# ArduFrauenfelderCNC_0_1-b9.net
KiCad netlist of a schematic drawn in EAGLE
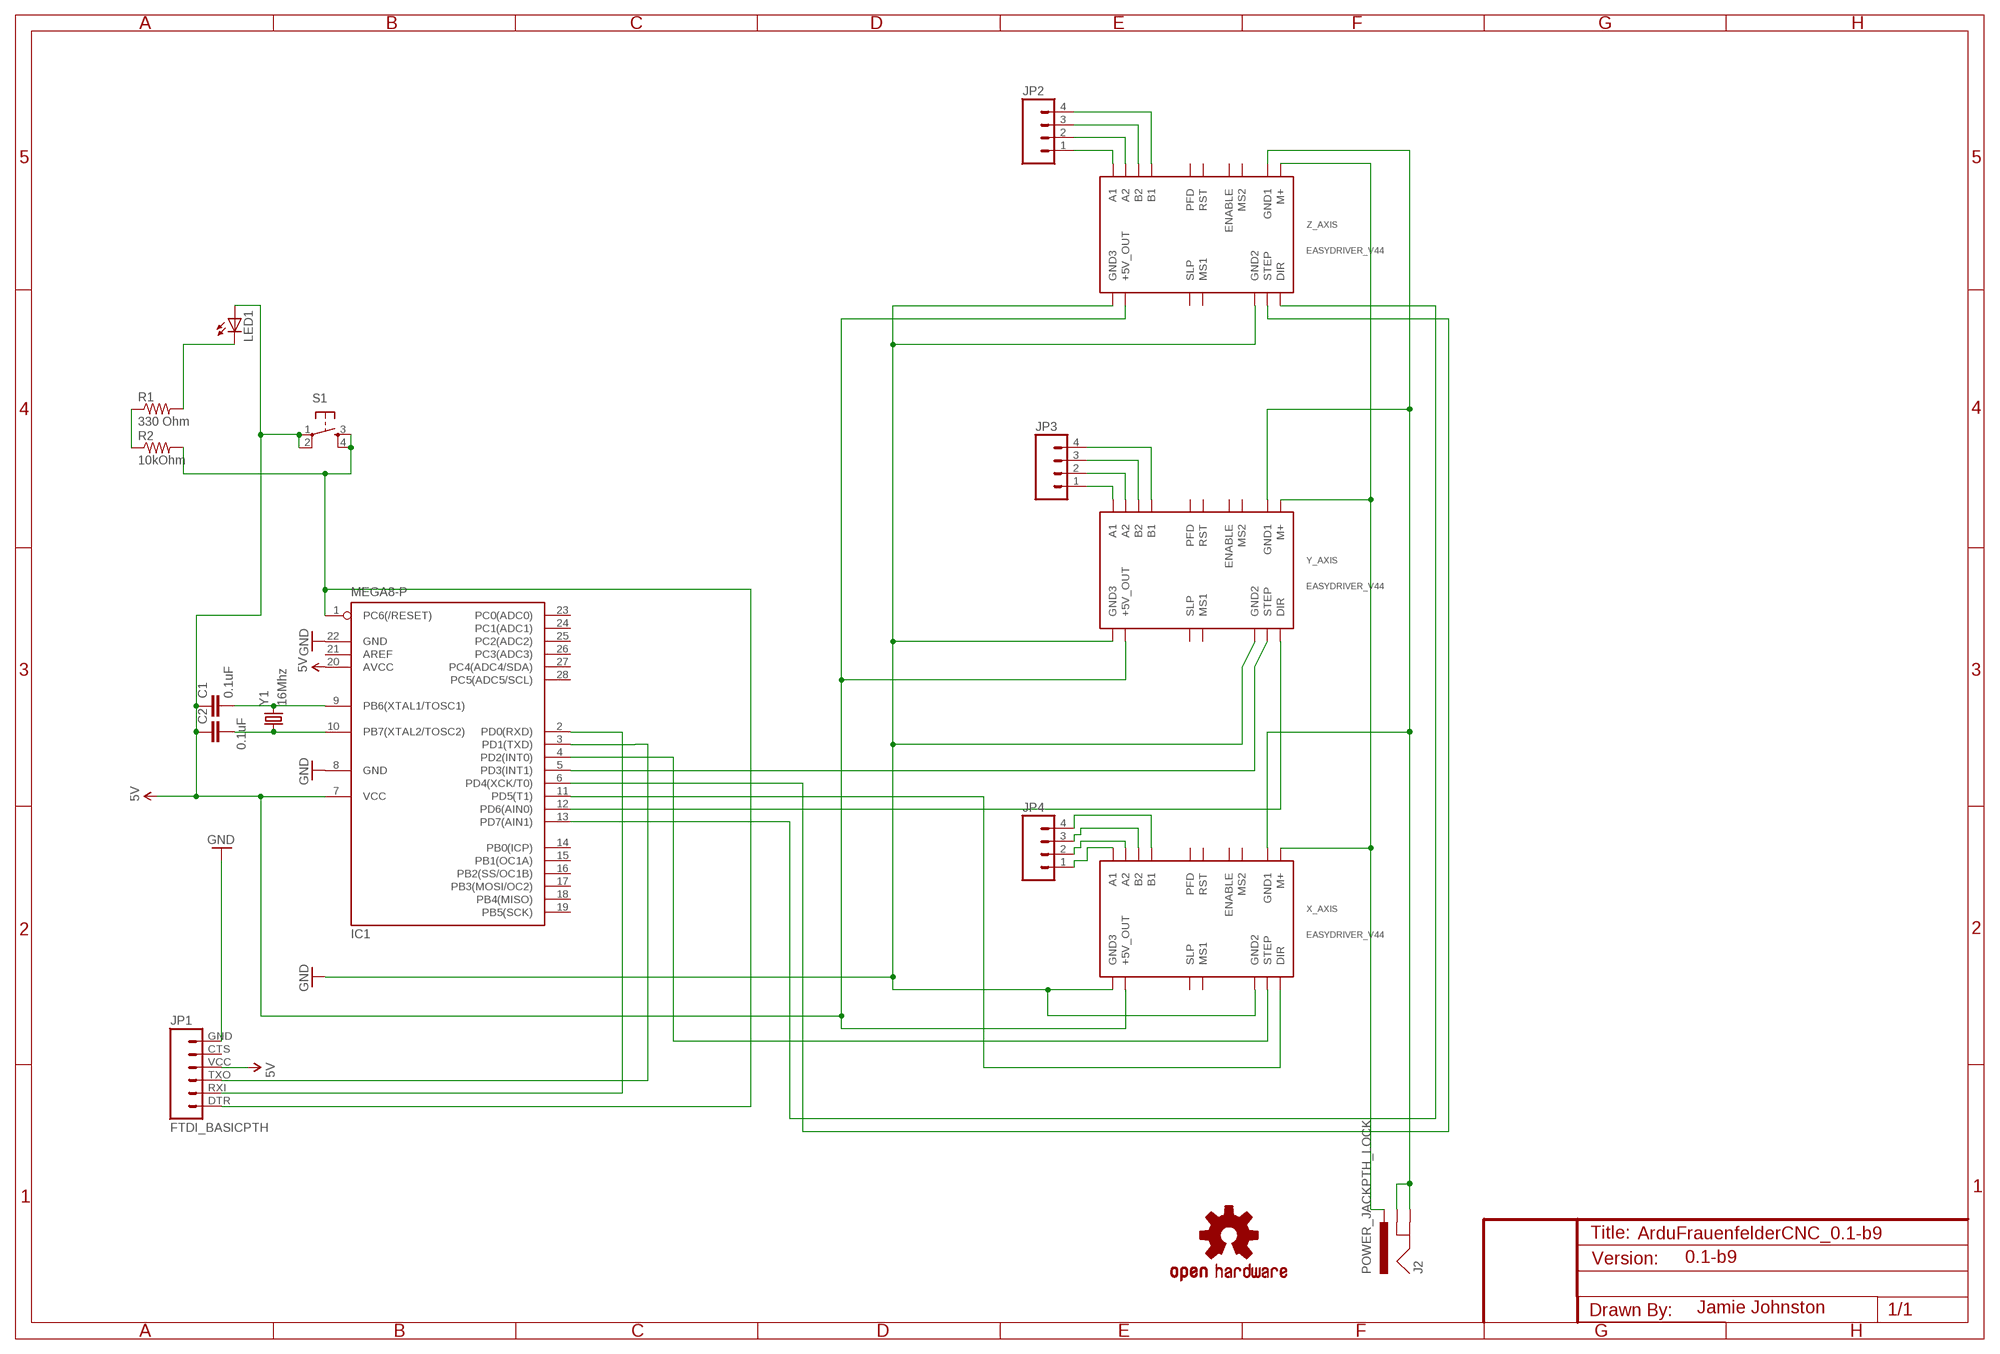
[diagram p0: schematic, sheet 1]

(export (version "E")
  (design (tool "Eeschema 10.0.6"))
  (components
    (comp (ref "C1")
      (value "0.1uF")
      (footprint "eagle-import:CAP-PTH-SMALL")
      (libsource (lib "eagle-import") (part "CAPPTH"))
    )
    (comp (ref "C2")
      (value "0.1uF")
      (footprint "eagle-import:CAP-PTH-SMALL")
      (libsource (lib "eagle-import") (part "CAPPTH"))
    )
    (comp (ref "IC1")
      (value "MEGA8-P")
      (footprint "eagle-import:DIL28-3")
      (libsource (lib "eagle-import") (part "MEGA8-P"))
    )
    (comp (ref "J2")
      (value "POWER_JACKPTH_LOCK")
      (footprint "eagle-import:POWER_JACK_PTH_LOCK")
      (libsource (lib "eagle-import") (part "POWER_JACKPTH_LOCK"))
    )
    (comp (ref "JP1")
      (value "FTDI_BASICPTH")
      (footprint "eagle-import:FTDI_BASIC")
      (libsource (lib "eagle-import") (part "FTDI_BASICPTH"))
    )
    (comp (ref "JP2")
      (value "M04LOCK")
      (footprint "eagle-import:1X04_LOCK")
      (libsource (lib "eagle-import") (part "M04LOCK"))
    )
    (comp (ref "JP3")
      (value "M04LOCK")
      (footprint "eagle-import:1X04_LOCK")
      (libsource (lib "eagle-import") (part "M04LOCK"))
    )
    (comp (ref "JP4")
      (value "M04LOCK")
      (footprint "eagle-import:1X04_LOCK")
      (libsource (lib "eagle-import") (part "M04LOCK"))
    )
    (comp (ref "LED1")
      (value "LED5MM")
      (footprint "eagle-import:LED5MM")
      (libsource (lib "eagle-import") (part "LED5MM"))
    )
    (comp (ref "R1")
      (value "330 Ohm")
      (footprint "eagle-import:AXIAL-0.4")
      (libsource (lib "eagle-import") (part "RESISTORPTH-1/4W"))
    )
    (comp (ref "R2")
      (value "10kOhm")
      (footprint "eagle-import:AXIAL-0.4")
      (libsource (lib "eagle-import") (part "RESISTORPTH-1/4W"))
    )
    (comp (ref "S1")
      (value "TAC_SWITCHPTH")
      (footprint "eagle-import:TACTILE-PTH")
      (libsource (lib "eagle-import") (part "TAC_SWITCHPTH"))
    )
    (comp (ref "U$2")
      (value "OSHW-LOGOL")
      (footprint "eagle-import:OSHW-LOGO-L")
      (libsource (lib "eagle-import") (part "OSHW-LOGOL"))
    )
    (comp (ref "X_AXIS")
      (value "EASYDRIVER_V44")
      (footprint "eagle-import:EASYDRIVER_V44")
      (libsource (lib "eagle-import") (part "EASYDRIVER_V44"))
    )
    (comp (ref "Y1")
      (value "16Mhz")
      (footprint "eagle-import:HC49US")
      (libsource (lib "eagle-import") (part "CRYSTALHC49US"))
    )
    (comp (ref "Y_AXIS")
      (value "EASYDRIVER_V44")
      (footprint "eagle-import:EASYDRIVER_V44")
      (libsource (lib "eagle-import") (part "EASYDRIVER_V44"))
    )
    (comp (ref "Z_AXIS")
      (value "EASYDRIVER_V44")
      (footprint "eagle-import:EASYDRIVER_V44")
      (libsource (lib "eagle-import") (part "EASYDRIVER_V44"))
    )
  )
  (nets
    (net (code "1") (name "5V") (class "Default")
      (node (ref "C1") (pin "1") (pinfunction "1_1") (pintype "passive"))
      (node (ref "C2") (pin "1") (pinfunction "1_1") (pintype "passive"))
      (node (ref "IC1") (pin "20") (pinfunction "AVCC_20") (pintype "power_in"))
      (node (ref "IC1") (pin "7") (pinfunction "VCC_7") (pintype "power_in"))
      (node (ref "JP1") (pin "VCC") (pinfunction "4_VCC") (pintype "passive"))
      (node (ref "LED1") (pin "A") (pinfunction "A_A") (pintype "passive"))
      (node (ref "S1") (pin "1") (pinfunction "1_1") (pintype "passive"))
      (node (ref "S1") (pin "2") (pinfunction "2_2") (pintype "passive"))
      (node (ref "X_AXIS") (pin "P$11") (pinfunction "+5V_OUT_P$11") (pintype "bidirectional"))
      (node (ref "Y_AXIS") (pin "P$11") (pinfunction "+5V_OUT_P$11") (pintype "bidirectional"))
      (node (ref "Z_AXIS") (pin "P$11") (pinfunction "+5V_OUT_P$11") (pintype "bidirectional"))
    )
    (net (code "2") (name "GND") (class "Default")
      (node (ref "IC1") (pin "22") (pinfunction "GND_22") (pintype "power_in"))
      (node (ref "IC1") (pin "8") (pinfunction "GND_8") (pintype "power_in"))
      (node (ref "JP1") (pin "GND") (pinfunction "6_GND") (pintype "passive"))
      (node (ref "X_AXIS") (pin "GND2") (pinfunction "GND2_GND2") (pintype "bidirectional"))
      (node (ref "X_AXIS") (pin "GND3") (pinfunction "GND3_GND3") (pintype "bidirectional"))
      (node (ref "Y_AXIS") (pin "GND2") (pinfunction "GND2_GND2") (pintype "bidirectional"))
      (node (ref "Y_AXIS") (pin "GND3") (pinfunction "GND3_GND3") (pintype "bidirectional"))
      (node (ref "Z_AXIS") (pin "GND2") (pinfunction "GND2_GND2") (pintype "bidirectional"))
      (node (ref "Z_AXIS") (pin "GND3") (pinfunction "GND3_GND3") (pintype "bidirectional"))
    )
    (net (code "3") (name "Net-(IC1-PB6(XTAL1{slash}TOSC1))") (class "Default")
      (node (ref "C1") (pin "2") (pinfunction "2_2") (pintype "passive"))
      (node (ref "IC1") (pin "9") (pinfunction "PB6(XTAL1/TOSC1)_9") (pintype "bidirectional"))
      (node (ref "Y1") (pin "2") (pinfunction "2_2") (pintype "passive"))
    )
    (net (code "4") (name "Net-(IC1-PB7(XTAL2{slash}TOSC2))") (class "Default")
      (node (ref "C2") (pin "2") (pinfunction "2_2") (pintype "passive"))
      (node (ref "IC1") (pin "10") (pinfunction "PB7(XTAL2/TOSC2)_10") (pintype "bidirectional"))
      (node (ref "Y1") (pin "1") (pinfunction "1_1") (pintype "passive"))
    )
    (net (code "5") (name "Net-(IC1-PC6({slash}RESET))") (class "Default")
      (node (ref "IC1") (pin "1") (pinfunction "PC6(/RESET)_1") (pintype "bidirectional"))
      (node (ref "JP1") (pin "DTR") (pinfunction "1_DTR") (pintype "passive"))
      (node (ref "R2") (pin "P$2") (pinfunction "2_P$2") (pintype "passive"))
      (node (ref "S1") (pin "3") (pinfunction "3_3") (pintype "passive"))
      (node (ref "S1") (pin "4") (pinfunction "4_4") (pintype "passive"))
    )
    (net (code "6") (name "Net-(IC1-PD0(RXD))") (class "Default")
      (node (ref "IC1") (pin "2") (pinfunction "PD0(RXD)_2") (pintype "bidirectional"))
      (node (ref "JP1") (pin "RXI") (pinfunction "2_RXI") (pintype "passive"))
    )
    (net (code "7") (name "Net-(IC1-PD1(TXD))") (class "Default")
      (node (ref "IC1") (pin "3") (pinfunction "PD1(TXD)_3") (pintype "bidirectional"))
      (node (ref "JP1") (pin "TXO") (pinfunction "3_TXO") (pintype "passive"))
    )
    (net (code "8") (name "Net-(IC1-PD2(INT0))") (class "Default")
      (node (ref "IC1") (pin "4") (pinfunction "PD2(INT0)_4") (pintype "bidirectional"))
      (node (ref "X_AXIS") (pin "STEP") (pinfunction "STEP_STEP") (pintype "bidirectional"))
    )
    (net (code "9") (name "Net-(IC1-PD3(INT1))") (class "Default")
      (node (ref "IC1") (pin "5") (pinfunction "PD3(INT1)_5") (pintype "bidirectional"))
      (node (ref "Y_AXIS") (pin "STEP") (pinfunction "STEP_STEP") (pintype "bidirectional"))
    )
    (net (code "10") (name "Net-(IC1-PD4(XCK{slash}T0))") (class "Default")
      (node (ref "IC1") (pin "6") (pinfunction "PD4(XCK/T0)_6") (pintype "bidirectional"))
      (node (ref "Z_AXIS") (pin "STEP") (pinfunction "STEP_STEP") (pintype "bidirectional"))
    )
    (net (code "11") (name "Net-(IC1-PD5(T1))") (class "Default")
      (node (ref "IC1") (pin "11") (pinfunction "PD5(T1)_11") (pintype "bidirectional"))
      (node (ref "X_AXIS") (pin "DIR") (pinfunction "DIR_DIR") (pintype "bidirectional"))
    )
    (net (code "12") (name "Net-(IC1-PD6(AIN0))") (class "Default")
      (node (ref "IC1") (pin "12") (pinfunction "PD6(AIN0)_12") (pintype "bidirectional"))
      (node (ref "Y_AXIS") (pin "DIR") (pinfunction "DIR_DIR") (pintype "bidirectional"))
    )
    (net (code "13") (name "Net-(IC1-PD7(AIN1))") (class "Default")
      (node (ref "IC1") (pin "13") (pinfunction "PD7(AIN1)_13") (pintype "bidirectional"))
      (node (ref "Z_AXIS") (pin "DIR") (pinfunction "DIR_DIR") (pintype "bidirectional"))
    )
    (net (code "14") (name "Net-(J2-PadGND)") (class "Default")
      (node (ref "J2") (pin "GND") (pinfunction "GND_GND") (pintype "bidirectional"))
      (node (ref "J2") (pin "GNDBREAK") (pinfunction "GNDBREAK_GNDBREAK") (pintype "bidirectional"))
      (node (ref "X_AXIS") (pin "GND1") (pinfunction "GND1_GND1") (pintype "bidirectional"))
      (node (ref "Y_AXIS") (pin "GND1") (pinfunction "GND1_GND1") (pintype "bidirectional"))
      (node (ref "Z_AXIS") (pin "GND1") (pinfunction "GND1_GND1") (pintype "bidirectional"))
    )
    (net (code "15") (name "Net-(J2-PadPWR)") (class "Default")
      (node (ref "J2") (pin "PWR") (pinfunction "PWR_PWR") (pintype "bidirectional"))
      (node (ref "X_AXIS") (pin "M+") (pinfunction "M+_M+") (pintype "bidirectional"))
      (node (ref "Y_AXIS") (pin "M+") (pinfunction "M+_M+") (pintype "bidirectional"))
      (node (ref "Z_AXIS") (pin "M+") (pinfunction "M+_M+") (pintype "bidirectional"))
    )
    (net (code "16") (name "Net-(JP2-Pad1)") (class "Default")
      (node (ref "JP2") (pin "1") (pinfunction "1_1") (pintype "passive"))
      (node (ref "Z_AXIS") (pin "A1") (pinfunction "A1_A1") (pintype "bidirectional"))
    )
    (net (code "17") (name "Net-(JP2-Pad2)") (class "Default")
      (node (ref "JP2") (pin "2") (pinfunction "2_2") (pintype "passive"))
      (node (ref "Z_AXIS") (pin "A2") (pinfunction "A2_A2") (pintype "bidirectional"))
    )
    (net (code "18") (name "Net-(JP2-Pad3)") (class "Default")
      (node (ref "JP2") (pin "3") (pinfunction "3_3") (pintype "passive"))
      (node (ref "Z_AXIS") (pin "B2") (pinfunction "B2_B2") (pintype "bidirectional"))
    )
    (net (code "19") (name "Net-(JP2-Pad4)") (class "Default")
      (node (ref "JP2") (pin "4") (pinfunction "4_4") (pintype "passive"))
      (node (ref "Z_AXIS") (pin "B1") (pinfunction "B1_B1") (pintype "bidirectional"))
    )
    (net (code "20") (name "Net-(JP3-Pad1)") (class "Default")
      (node (ref "JP3") (pin "1") (pinfunction "1_1") (pintype "passive"))
      (node (ref "Y_AXIS") (pin "A1") (pinfunction "A1_A1") (pintype "bidirectional"))
    )
    (net (code "21") (name "Net-(JP3-Pad2)") (class "Default")
      (node (ref "JP3") (pin "2") (pinfunction "2_2") (pintype "passive"))
      (node (ref "Y_AXIS") (pin "A2") (pinfunction "A2_A2") (pintype "bidirectional"))
    )
    (net (code "22") (name "Net-(JP3-Pad3)") (class "Default")
      (node (ref "JP3") (pin "3") (pinfunction "3_3") (pintype "passive"))
      (node (ref "Y_AXIS") (pin "B2") (pinfunction "B2_B2") (pintype "bidirectional"))
    )
    (net (code "23") (name "Net-(JP3-Pad4)") (class "Default")
      (node (ref "JP3") (pin "4") (pinfunction "4_4") (pintype "passive"))
      (node (ref "Y_AXIS") (pin "B1") (pinfunction "B1_B1") (pintype "bidirectional"))
    )
    (net (code "24") (name "Net-(JP4-Pad1)") (class "Default")
      (node (ref "JP4") (pin "1") (pinfunction "1_1") (pintype "passive"))
      (node (ref "X_AXIS") (pin "A1") (pinfunction "A1_A1") (pintype "bidirectional"))
    )
    (net (code "25") (name "Net-(JP4-Pad2)") (class "Default")
      (node (ref "JP4") (pin "2") (pinfunction "2_2") (pintype "passive"))
      (node (ref "X_AXIS") (pin "A2") (pinfunction "A2_A2") (pintype "bidirectional"))
    )
    (net (code "26") (name "Net-(JP4-Pad3)") (class "Default")
      (node (ref "JP4") (pin "3") (pinfunction "3_3") (pintype "passive"))
      (node (ref "X_AXIS") (pin "B2") (pinfunction "B2_B2") (pintype "bidirectional"))
    )
    (net (code "27") (name "Net-(JP4-Pad4)") (class "Default")
      (node (ref "JP4") (pin "4") (pinfunction "4_4") (pintype "passive"))
      (node (ref "X_AXIS") (pin "B1") (pinfunction "B1_B1") (pintype "bidirectional"))
    )
    (net (code "28") (name "Net-(LED1-C)") (class "Default")
      (node (ref "LED1") (pin "K") (pinfunction "C_K") (pintype "passive"))
      (node (ref "R1") (pin "P$2") (pinfunction "2_P$2") (pintype "passive"))
    )
    (net (code "29") (name "Net-(R1-1)") (class "Default")
      (node (ref "R1") (pin "P$1") (pinfunction "1_P$1") (pintype "passive"))
      (node (ref "R2") (pin "P$1") (pinfunction "1_P$1") (pintype "passive"))
    )
    (net (code "30") (name "unconnected-(IC1-AREF-Pad21)") (class "Default")
      (node (ref "IC1") (pin "21") (pinfunction "AREF_21") (pintype "passive"))
    )
    (net (code "31") (name "unconnected-(IC1-PB0(ICP)-Pad14)") (class "Default")
      (node (ref "IC1") (pin "14") (pinfunction "PB0(ICP)_14") (pintype "bidirectional"))
    )
    (net (code "32") (name "unconnected-(IC1-PB1(OC1A)-Pad15)") (class "Default")
      (node (ref "IC1") (pin "15") (pinfunction "PB1(OC1A)_15") (pintype "bidirectional"))
    )
    (net (code "33") (name "unconnected-(IC1-PB2(SS{slash}OC1B)-Pad16)") (class "Default")
      (node (ref "IC1") (pin "16") (pinfunction "PB2(SS/OC1B)_16") (pintype "bidirectional"))
    )
    (net (code "34") (name "unconnected-(IC1-PB3(MOSI{slash}OC2)-Pad17)") (class "Default")
      (node (ref "IC1") (pin "17") (pinfunction "PB3(MOSI/OC2)_17") (pintype "bidirectional"))
    )
    (net (code "35") (name "unconnected-(IC1-PB4(MISO)-Pad18)") (class "Default")
      (node (ref "IC1") (pin "18") (pinfunction "PB4(MISO)_18") (pintype "bidirectional"))
    )
    (net (code "36") (name "unconnected-(IC1-PB5(SCK)-Pad19)") (class "Default")
      (node (ref "IC1") (pin "19") (pinfunction "PB5(SCK)_19") (pintype "bidirectional"))
    )
    (net (code "37") (name "unconnected-(IC1-PC0(ADC0)-Pad23)") (class "Default")
      (node (ref "IC1") (pin "23") (pinfunction "PC0(ADC0)_23") (pintype "bidirectional"))
    )
    (net (code "38") (name "unconnected-(IC1-PC1(ADC1)-Pad24)") (class "Default")
      (node (ref "IC1") (pin "24") (pinfunction "PC1(ADC1)_24") (pintype "bidirectional"))
    )
    (net (code "39") (name "unconnected-(IC1-PC2(ADC2)-Pad25)") (class "Default")
      (node (ref "IC1") (pin "25") (pinfunction "PC2(ADC2)_25") (pintype "bidirectional"))
    )
    (net (code "40") (name "unconnected-(IC1-PC3(ADC3)-Pad26)") (class "Default")
      (node (ref "IC1") (pin "26") (pinfunction "PC3(ADC3)_26") (pintype "bidirectional"))
    )
    (net (code "41") (name "unconnected-(IC1-PC4(ADC4{slash}SDA)-Pad27)") (class "Default")
      (node (ref "IC1") (pin "27") (pinfunction "PC4(ADC4/SDA)_27") (pintype "bidirectional"))
    )
    (net (code "42") (name "unconnected-(IC1-PC5(ADC5{slash}SCL)-Pad28)") (class "Default")
      (node (ref "IC1") (pin "28") (pinfunction "PC5(ADC5/SCL)_28") (pintype "bidirectional"))
    )
    (net (code "43") (name "unconnected-(JP1-5-PadCTS)") (class "Default")
      (node (ref "JP1") (pin "CTS") (pinfunction "5_CTS") (pintype "passive"))
    )
    (net (code "44") (name "unconnected-(X_AXIS-PadENABLE)") (class "Default")
      (node (ref "X_AXIS") (pin "ENABLE") (pinfunction "ENABLE_ENABLE") (pintype "bidirectional"))
    )
    (net (code "45") (name "unconnected-(X_AXIS-PadMS1)") (class "Default")
      (node (ref "X_AXIS") (pin "MS1") (pinfunction "MS1_MS1") (pintype "bidirectional"))
    )
    (net (code "46") (name "unconnected-(X_AXIS-PadMS2)") (class "Default")
      (node (ref "X_AXIS") (pin "MS2") (pinfunction "MS2_MS2") (pintype "bidirectional"))
    )
    (net (code "47") (name "unconnected-(X_AXIS-PadPFD)") (class "Default")
      (node (ref "X_AXIS") (pin "PFD") (pinfunction "PFD_PFD") (pintype "bidirectional"))
    )
    (net (code "48") (name "unconnected-(X_AXIS-PadRST)") (class "Default")
      (node (ref "X_AXIS") (pin "RST") (pinfunction "RST_RST") (pintype "bidirectional"))
    )
    (net (code "49") (name "unconnected-(X_AXIS-SLP-PadSLEEP)") (class "Default")
      (node (ref "X_AXIS") (pin "SLEEP") (pinfunction "SLP_SLEEP") (pintype "bidirectional"))
    )
    (net (code "50") (name "unconnected-(Y_AXIS-PadENABLE)") (class "Default")
      (node (ref "Y_AXIS") (pin "ENABLE") (pinfunction "ENABLE_ENABLE") (pintype "bidirectional"))
    )
    (net (code "51") (name "unconnected-(Y_AXIS-PadMS1)") (class "Default")
      (node (ref "Y_AXIS") (pin "MS1") (pinfunction "MS1_MS1") (pintype "bidirectional"))
    )
    (net (code "52") (name "unconnected-(Y_AXIS-PadMS2)") (class "Default")
      (node (ref "Y_AXIS") (pin "MS2") (pinfunction "MS2_MS2") (pintype "bidirectional"))
    )
    (net (code "53") (name "unconnected-(Y_AXIS-PadPFD)") (class "Default")
      (node (ref "Y_AXIS") (pin "PFD") (pinfunction "PFD_PFD") (pintype "bidirectional"))
    )
    (net (code "54") (name "unconnected-(Y_AXIS-PadRST)") (class "Default")
      (node (ref "Y_AXIS") (pin "RST") (pinfunction "RST_RST") (pintype "bidirectional"))
    )
    (net (code "55") (name "unconnected-(Y_AXIS-SLP-PadSLEEP)") (class "Default")
      (node (ref "Y_AXIS") (pin "SLEEP") (pinfunction "SLP_SLEEP") (pintype "bidirectional"))
    )
    (net (code "56") (name "unconnected-(Z_AXIS-PadENABLE)") (class "Default")
      (node (ref "Z_AXIS") (pin "ENABLE") (pinfunction "ENABLE_ENABLE") (pintype "bidirectional"))
    )
    (net (code "57") (name "unconnected-(Z_AXIS-PadMS1)") (class "Default")
      (node (ref "Z_AXIS") (pin "MS1") (pinfunction "MS1_MS1") (pintype "bidirectional"))
    )
    (net (code "58") (name "unconnected-(Z_AXIS-PadMS2)") (class "Default")
      (node (ref "Z_AXIS") (pin "MS2") (pinfunction "MS2_MS2") (pintype "bidirectional"))
    )
    (net (code "59") (name "unconnected-(Z_AXIS-PadPFD)") (class "Default")
      (node (ref "Z_AXIS") (pin "PFD") (pinfunction "PFD_PFD") (pintype "bidirectional"))
    )
    (net (code "60") (name "unconnected-(Z_AXIS-PadRST)") (class "Default")
      (node (ref "Z_AXIS") (pin "RST") (pinfunction "RST_RST") (pintype "bidirectional"))
    )
    (net (code "61") (name "unconnected-(Z_AXIS-SLP-PadSLEEP)") (class "Default")
      (node (ref "Z_AXIS") (pin "SLEEP") (pinfunction "SLP_SLEEP") (pintype "bidirectional"))
    )
  )
)
